# AD_Converter.net
KiCad netlist of a schematic drawn in Altium Designer
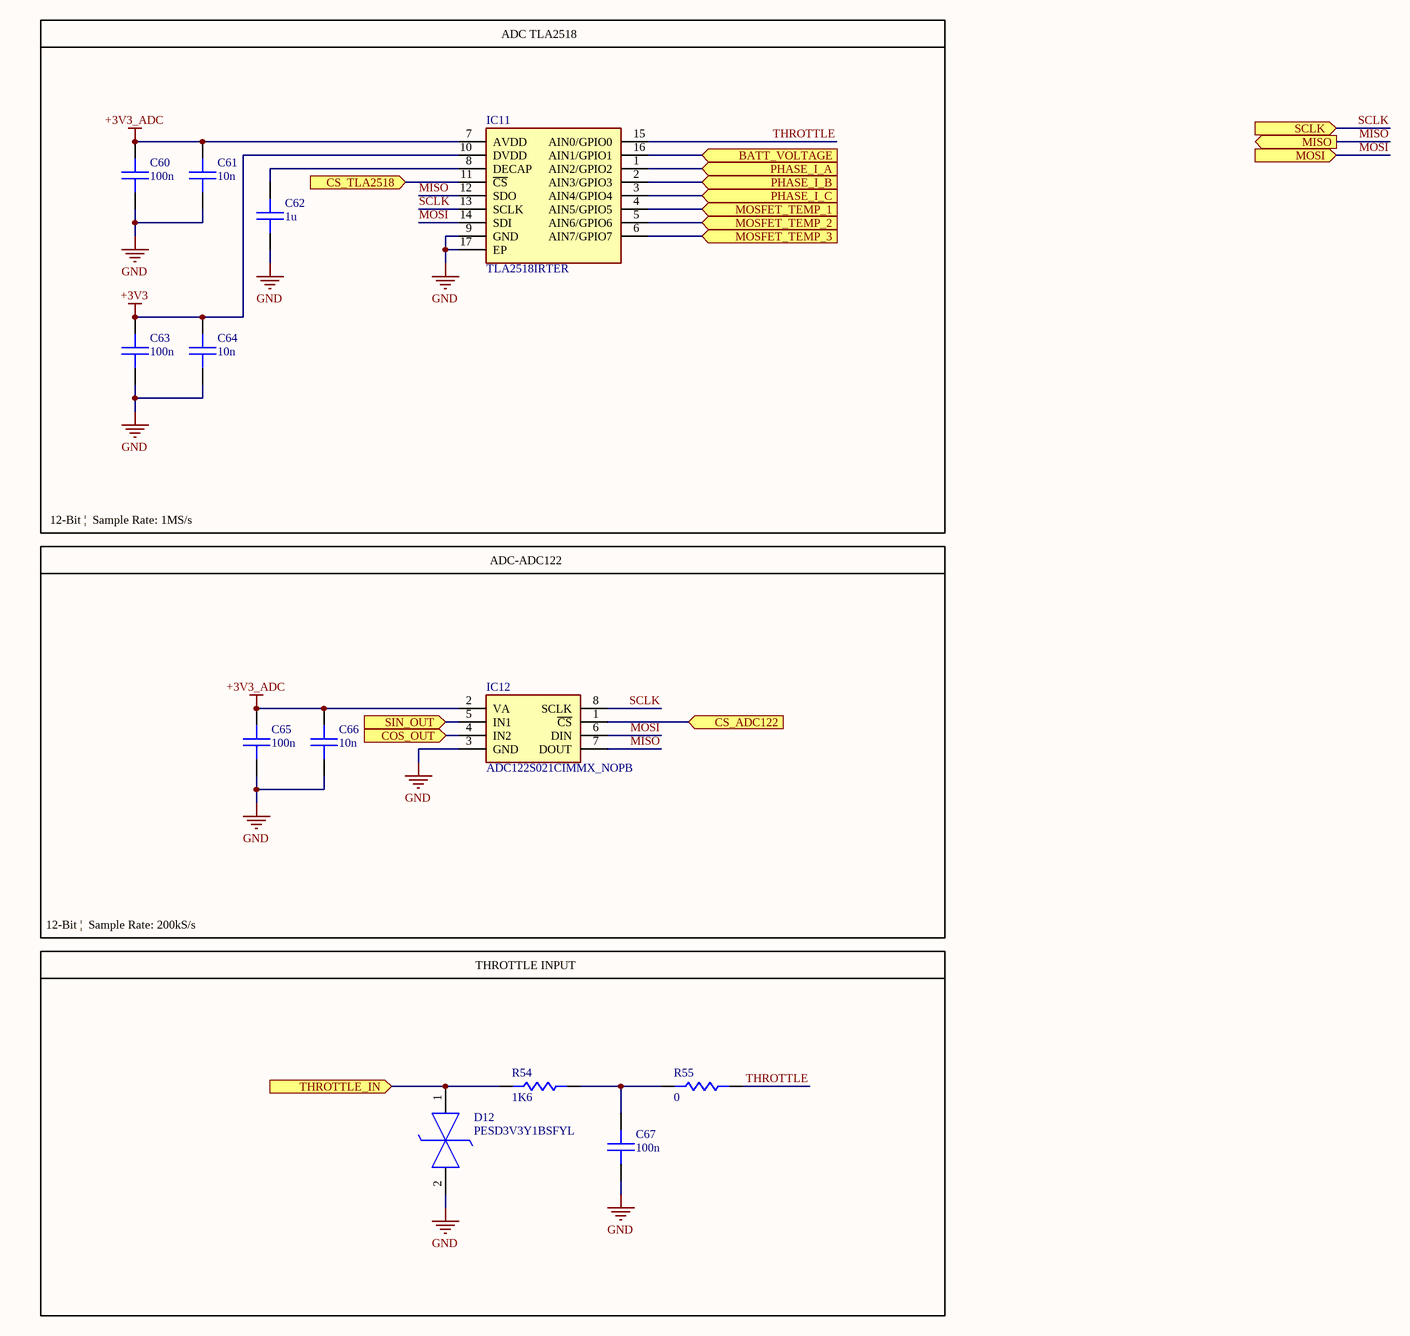
[diagram p0: AD_Converter.SchDoc]

(export (version "E")
  (design (tool "Eeschema 10.0.6"))
  (components
    (comp (ref "C60")
      (value "100n")
      (footprint "C_0603")
      (description "SMD Chip Capacitor")
      (libsource (lib "My_Integrated_Lib") (part "CAP"))
    )
    (comp (ref "C61")
      (value "10n")
      (footprint "C_0603")
      (description "SMD Chip Capacitor")
      (libsource (lib "My_Integrated_Lib") (part "CAP"))
    )
    (comp (ref "C62")
      (value "1u")
      (footprint "C_0603")
      (description "SMD Chip Capacitor")
      (libsource (lib "My_Integrated_Lib") (part "CAP"))
    )
    (comp (ref "C63")
      (value "100n")
      (footprint "C_0603")
      (description "SMD Chip Capacitor")
      (libsource (lib "My_Integrated_Lib") (part "CAP"))
    )
    (comp (ref "C64")
      (value "10n")
      (footprint "C_0603")
      (description "SMD Chip Capacitor")
      (libsource (lib "My_Integrated_Lib") (part "CAP"))
    )
    (comp (ref "C65")
      (value "100n")
      (footprint "C_0603")
      (description "SMD Chip Capacitor")
      (libsource (lib "My_Integrated_Lib") (part "CAP"))
    )
    (comp (ref "C66")
      (value "10n")
      (footprint "C_0603")
      (description "SMD Chip Capacitor")
      (libsource (lib "My_Integrated_Lib") (part "CAP"))
    )
    (comp (ref "C67")
      (value "100n")
      (footprint "C_0603")
      (description "SMD Chip Capacitor")
      (libsource (lib "My_Integrated_Lib") (part "CAP"))
    )
    (comp (ref "D12")
      (value "PESD3V3Y1BSFYL")
      (footprint "PMEG3005AESFYL")
      (description "Diode ESD (Bi-directional)")
      (fields (field (name "MOUSER PART NUMBER") "771-PESD3V3Y1BSFYL"))
      (libsource (lib "My_Integrated_Lib") (part "PESD3V3Y1BSFYL"))
    )
    (comp (ref "IC11")
      (value "TLA2518IRTER")
      (footprint "QFN50P300X300X80-17N-D")
      (description "Integrated Circuit")
      (fields (field (name "MOUSER PART NUMBER") "595-TLA2518IRTER"))
      (libsource (lib "My_Integrated_Lib") (part "TLA2518IRTER"))
    )
    (comp (ref "IC12")
      (value "ADC122S021CIMMX_NOPB")
      (footprint "SOP65P490X110-8N")
      (description "Integrated Circuit")
      (fields
        (field (name "MANUFACTURER_PART_NUMBER") "ADC122S021CIMMX/NOPB")
        (field (name "MOUSER PART NUMBER") "926-A122S021CIMMXNPB")
      )
      (libsource (lib "My_Integrated_Lib") (part "ADC122S021CIMMX_NOPB"))
    )
    (comp (ref "R54")
      (value "1K6")
      (footprint "R_0603")
      (description "SMD Chip Resistor")
      (libsource (lib "My_Integrated_Lib") (part "RES"))
    )
    (comp (ref "R55")
      (value "0")
      (footprint "R_0603")
      (description "SMD Chip Resistor")
      (libsource (lib "My_Integrated_Lib") (part "RES"))
    )
  )
  (nets
    (net (code "1") (name "+3V3") (class "Default")
      (node (ref "C63") (pin "2") (pinfunction "2_2") (pintype "passive"))
      (node (ref "C64") (pin "2") (pinfunction "2_2") (pintype "passive"))
      (node (ref "IC11") (pin "10") (pinfunction "DVDD_10") (pintype "passive"))
    )
    (net (code "2") (name "+3V3_ADC") (class "Default")
      (node (ref "C60") (pin "2") (pinfunction "2_2") (pintype "passive"))
      (node (ref "C61") (pin "2") (pinfunction "2_2") (pintype "passive"))
      (node (ref "C65") (pin "2") (pinfunction "2_2") (pintype "passive"))
      (node (ref "C66") (pin "2") (pinfunction "2_2") (pintype "passive"))
      (node (ref "IC11") (pin "7") (pinfunction "AVDD_7") (pintype "passive"))
      (node (ref "IC12") (pin "2") (pinfunction "VA_2") (pintype "passive"))
    )
    (net (code "3") (name "/BATT_VOLTAGE") (class "Default")
      (node (ref "IC11") (pin "16") (pinfunction "AIN1/GPIO1_16") (pintype "passive"))
    )
    (net (code "4") (name "/COS_OUT") (class "Default")
      (node (ref "IC12") (pin "4") (pinfunction "IN2_4") (pintype "passive"))
    )
    (net (code "5") (name "/CS_ADC122") (class "Default")
      (node (ref "IC12") (pin "1") (pinfunction "~{CS}_1") (pintype "passive"))
    )
    (net (code "6") (name "/CS_TLA2518") (class "Default")
      (node (ref "IC11") (pin "11") (pinfunction "~{CS}_11") (pintype "passive"))
    )
    (net (code "7") (name "/MISO") (class "Default")
      (node (ref "IC11") (pin "12") (pinfunction "SDO_12") (pintype "passive"))
      (node (ref "IC12") (pin "7") (pinfunction "DOUT_7") (pintype "passive"))
    )
    (net (code "8") (name "/MOSFET_TEMP_1") (class "Default")
      (node (ref "IC11") (pin "4") (pinfunction "AIN5/GPIO5_4") (pintype "passive"))
    )
    (net (code "9") (name "/MOSFET_TEMP_2") (class "Default")
      (node (ref "IC11") (pin "5") (pinfunction "AIN6/GPIO6_5") (pintype "passive"))
    )
    (net (code "10") (name "/MOSFET_TEMP_3") (class "Default")
      (node (ref "IC11") (pin "6") (pinfunction "AIN7/GPIO7_6") (pintype "passive"))
    )
    (net (code "11") (name "/MOSI") (class "Default")
      (node (ref "IC11") (pin "14") (pinfunction "SDI_14") (pintype "passive"))
      (node (ref "IC12") (pin "6") (pinfunction "DIN_6") (pintype "passive"))
    )
    (net (code "12") (name "/PHASE_I_A") (class "Default")
      (node (ref "IC11") (pin "1") (pinfunction "AIN2/GPIO2_1") (pintype "passive"))
    )
    (net (code "13") (name "/PHASE_I_B") (class "Default")
      (node (ref "IC11") (pin "2") (pinfunction "AIN3/GPIO3_2") (pintype "passive"))
    )
    (net (code "14") (name "/PHASE_I_C") (class "Default")
      (node (ref "IC11") (pin "3") (pinfunction "AIN4/GPIO4_3") (pintype "passive"))
    )
    (net (code "15") (name "/SCLK") (class "Default")
      (node (ref "IC11") (pin "13") (pinfunction "SCLK_13") (pintype "passive"))
      (node (ref "IC12") (pin "8") (pinfunction "SCLK_8") (pintype "passive"))
    )
    (net (code "16") (name "/SIN_OUT") (class "Default")
      (node (ref "IC12") (pin "5") (pinfunction "IN1_5") (pintype "passive"))
    )
    (net (code "17") (name "/THROTTLE") (class "Default")
      (node (ref "IC11") (pin "15") (pinfunction "AIN0/GPIO0_15") (pintype "passive"))
      (node (ref "R55") (pin "1") (pinfunction "1_1") (pintype "passive"))
    )
    (net (code "18") (name "/THROTTLE_IN") (class "Default")
      (node (ref "D12") (pin "1") (pinfunction "K1_1") (pintype "passive"))
      (node (ref "R54") (pin "2") (pinfunction "2_2") (pintype "passive"))
    )
    (net (code "19") (name "GND") (class "Default")
      (node (ref "C60") (pin "1") (pinfunction "1_1") (pintype "passive"))
      (node (ref "C61") (pin "1") (pinfunction "1_1") (pintype "passive"))
      (node (ref "C62") (pin "1") (pinfunction "1_1") (pintype "passive"))
      (node (ref "C63") (pin "1") (pinfunction "1_1") (pintype "passive"))
      (node (ref "C64") (pin "1") (pinfunction "1_1") (pintype "passive"))
      (node (ref "C65") (pin "1") (pinfunction "1_1") (pintype "passive"))
      (node (ref "C66") (pin "1") (pinfunction "1_1") (pintype "passive"))
      (node (ref "C67") (pin "1") (pinfunction "1_1") (pintype "passive"))
      (node (ref "D12") (pin "2") (pinfunction "K2_2") (pintype "passive"))
      (node (ref "IC11") (pin "17") (pinfunction "EP_17") (pintype "passive"))
      (node (ref "IC11") (pin "9") (pinfunction "GND_9") (pintype "passive"))
      (node (ref "IC12") (pin "3") (pinfunction "GND_3") (pintype "passive"))
    )
    (net (code "20") (name "Net-(C67-Pad2)") (class "Default")
      (node (ref "C67") (pin "2") (pinfunction "2_2") (pintype "passive"))
      (node (ref "R54") (pin "1") (pinfunction "1_1") (pintype "passive"))
      (node (ref "R55") (pin "2") (pinfunction "2_2") (pintype "passive"))
    )
    (net (code "21") (name "Net-(IC11-DECAP)") (class "Default")
      (node (ref "C62") (pin "2") (pinfunction "2_2") (pintype "passive"))
      (node (ref "IC11") (pin "8") (pinfunction "DECAP_8") (pintype "passive"))
    )
  )
)
